# camera_and_stage.net
KiCad netlist of a schematic drawn in EAGLE
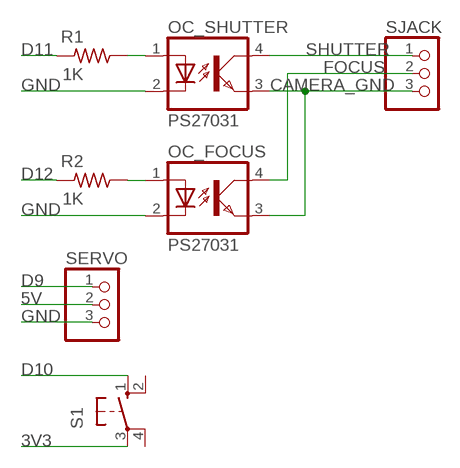
[diagram p0: schematic, sheet 1]

(export (version "E")
  (design (tool "Eeschema 10.0.6"))
  (components
    (comp (ref "OC_FOCUS")
      (value "PS27031")
      (footprint "eagle-import:SMD4")
      (fields (field (name "OC_FARNELL") "unknown") (field (name "OC_NEWARK") "unknown"))
      (libsource (lib "eagle-import") (part "PS27031"))
    )
    (comp (ref "OC_SHUTTER")
      (value "PS27031")
      (footprint "eagle-import:SMD4")
      (libsource (lib "eagle-import") (part "PS27031"))
    )
    (comp (ref "R1")
      (value "1K")
      (footprint "eagle-import:0204_7")
      (libsource (lib "eagle-import") (part "R-US_0204/7"))
    )
    (comp (ref "R2")
      (value "1K")
      (footprint "eagle-import:0204_7")
      (libsource (lib "eagle-import") (part "R-US_0204/7"))
    )
    (comp (ref "S1")
      (value "10-XX")
      (footprint "eagle-import:B3F-10XX")
      (fields (field (name "MPN") "B3F-1000"))
      (libsource (lib "eagle-import") (part "10-XX"))
    )
    (comp (ref "SERVO")
      (value "PINHD-1X3")
      (footprint "eagle-import:1X03")
      (libsource (lib "eagle-import") (part "PINHD-1X3"))
    )
    (comp (ref "SJACK")
      (value "PINHD-1X3")
      (footprint "eagle-import:1X03")
      (libsource (lib "eagle-import") (part "PINHD-1X3"))
    )
  )
  (nets
    (net (code "1") (name "/3V3") (class "Default")
      (node (ref "S1") (pin "3") (pinfunction "P_3") (pintype "passive"))
    )
    (net (code "2") (name "/5V") (class "Default")
      (node (ref "SERVO") (pin "2") (pinfunction "2_2") (pintype "passive"))
    )
    (net (code "3") (name "/CAMERA_GND") (class "Default")
      (node (ref "OC_FOCUS") (pin "3") (pinfunction "EMIT_3") (pintype "passive"))
      (node (ref "OC_SHUTTER") (pin "3") (pinfunction "EMIT_3") (pintype "passive"))
      (node (ref "SJACK") (pin "3") (pinfunction "3_3") (pintype "passive"))
    )
    (net (code "4") (name "/D9") (class "Default")
      (node (ref "SERVO") (pin "1") (pinfunction "1_1") (pintype "passive"))
    )
    (net (code "5") (name "/D10") (class "Default")
      (node (ref "S1") (pin "1") (pinfunction "S_1") (pintype "passive"))
    )
    (net (code "6") (name "/D11") (class "Default")
      (node (ref "R1") (pin "2") (pinfunction "2_2") (pintype "passive"))
    )
    (net (code "7") (name "/D12") (class "Default")
      (node (ref "R2") (pin "2") (pinfunction "2_2") (pintype "passive"))
    )
    (net (code "8") (name "/FOCUS") (class "Default")
      (node (ref "OC_FOCUS") (pin "4") (pinfunction "COL_4") (pintype "passive"))
      (node (ref "SJACK") (pin "2") (pinfunction "2_2") (pintype "passive"))
    )
    (net (code "9") (name "/GND") (class "Default")
      (node (ref "OC_FOCUS") (pin "2") (pinfunction "C_2") (pintype "passive"))
      (node (ref "OC_SHUTTER") (pin "2") (pinfunction "C_2") (pintype "passive"))
      (node (ref "SERVO") (pin "3") (pinfunction "3_3") (pintype "passive"))
    )
    (net (code "10") (name "/SHUTTER") (class "Default")
      (node (ref "OC_SHUTTER") (pin "4") (pinfunction "COL_4") (pintype "passive"))
      (node (ref "SJACK") (pin "1") (pinfunction "1_1") (pintype "passive"))
    )
    (net (code "11") (name "Net-(OC_FOCUS-A)") (class "Default")
      (node (ref "OC_FOCUS") (pin "1") (pinfunction "A_1") (pintype "passive"))
      (node (ref "R2") (pin "1") (pinfunction "1_1") (pintype "passive"))
    )
    (net (code "12") (name "Net-(OC_SHUTTER-A)") (class "Default")
      (node (ref "OC_SHUTTER") (pin "1") (pinfunction "A_1") (pintype "passive"))
      (node (ref "R1") (pin "1") (pinfunction "1_1") (pintype "passive"))
    )
    (net (code "13") (name "unconnected-(S1-P1-Pad4)") (class "Default")
      (node (ref "S1") (pin "4") (pinfunction "P1_4") (pintype "passive"))
    )
    (net (code "14") (name "unconnected-(S1-S1-Pad2)") (class "Default")
      (node (ref "S1") (pin "2") (pinfunction "S1_2") (pintype "passive"))
    )
  )
)
